# LCD_CONNECTORS.net
KiCad netlist of a schematic drawn in Altium Designer
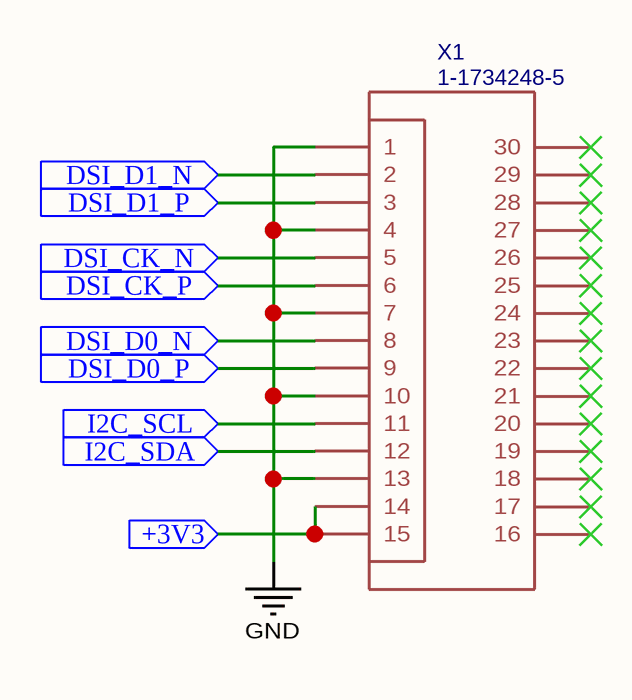
[diagram p0: LCD CONNECTORS.schdoc]

(export (version "E")
  (design (tool "Eeschema 10.0.6"))
  (components
    (comp (ref "X1")
      (value "1-1734248-5")
      (fields (field (name "CONTRIBUTOR") "IBE_Acc"))
      (libsource (lib "altium-import") (part "root_0_1-1734248-5_"))
    )
  )
  (nets
    (net (code "1") (name "/+3V3") (class "Default")
      (node (ref "X1") (pin "14") (pinfunction "14_14") (pintype "passive"))
      (node (ref "X1") (pin "15") (pinfunction "15_15") (pintype "passive"))
    )
    (net (code "2") (name "/DSI_CK_N") (class "Default")
      (node (ref "X1") (pin "5") (pinfunction "5_5") (pintype "passive"))
    )
    (net (code "3") (name "/DSI_CK_P") (class "Default")
      (node (ref "X1") (pin "6") (pinfunction "6_6") (pintype "passive"))
    )
    (net (code "4") (name "/DSI_D0_N") (class "Default")
      (node (ref "X1") (pin "8") (pinfunction "8_8") (pintype "passive"))
    )
    (net (code "5") (name "/DSI_D0_P") (class "Default")
      (node (ref "X1") (pin "9") (pinfunction "9_9") (pintype "passive"))
    )
    (net (code "6") (name "/DSI_D1_N") (class "Default")
      (node (ref "X1") (pin "2") (pinfunction "2_2") (pintype "passive"))
    )
    (net (code "7") (name "/DSI_D1_P") (class "Default")
      (node (ref "X1") (pin "3") (pinfunction "3_3") (pintype "passive"))
    )
    (net (code "8") (name "/I2C_SCL") (class "Default")
      (node (ref "X1") (pin "11") (pinfunction "11_11") (pintype "passive"))
    )
    (net (code "9") (name "/I2C_SDA") (class "Default")
      (node (ref "X1") (pin "12") (pinfunction "12_12") (pintype "passive"))
    )
    (net (code "10") (name "GND") (class "Default")
      (node (ref "X1") (pin "1") (pinfunction "1_1") (pintype "passive"))
      (node (ref "X1") (pin "10") (pinfunction "10_10") (pintype "passive"))
      (node (ref "X1") (pin "13") (pinfunction "13_13") (pintype "passive"))
      (node (ref "X1") (pin "4") (pinfunction "4_4") (pintype "passive"))
      (node (ref "X1") (pin "7") (pinfunction "7_7") (pintype "passive"))
    )
    (net (code "11") (name "unconnected-(X1-Pad16)") (class "Default")
      (node (ref "X1") (pin "16") (pinfunction "16_16") (pintype "passive+no_connect"))
    )
    (net (code "12") (name "unconnected-(X1-Pad17)") (class "Default")
      (node (ref "X1") (pin "17") (pinfunction "17_17") (pintype "passive+no_connect"))
    )
    (net (code "13") (name "unconnected-(X1-Pad18)") (class "Default")
      (node (ref "X1") (pin "18") (pinfunction "18_18") (pintype "passive+no_connect"))
    )
    (net (code "14") (name "unconnected-(X1-Pad19)") (class "Default")
      (node (ref "X1") (pin "19") (pinfunction "19_19") (pintype "passive+no_connect"))
    )
    (net (code "15") (name "unconnected-(X1-Pad20)") (class "Default")
      (node (ref "X1") (pin "20") (pinfunction "20_20") (pintype "passive+no_connect"))
    )
    (net (code "16") (name "unconnected-(X1-Pad21)") (class "Default")
      (node (ref "X1") (pin "21") (pinfunction "21_21") (pintype "passive+no_connect"))
    )
    (net (code "17") (name "unconnected-(X1-Pad22)") (class "Default")
      (node (ref "X1") (pin "22") (pinfunction "22_22") (pintype "passive+no_connect"))
    )
    (net (code "18") (name "unconnected-(X1-Pad23)") (class "Default")
      (node (ref "X1") (pin "23") (pinfunction "23_23") (pintype "passive+no_connect"))
    )
    (net (code "19") (name "unconnected-(X1-Pad24)") (class "Default")
      (node (ref "X1") (pin "24") (pinfunction "24_24") (pintype "passive+no_connect"))
    )
    (net (code "20") (name "unconnected-(X1-Pad25)") (class "Default")
      (node (ref "X1") (pin "25") (pinfunction "25_25") (pintype "passive+no_connect"))
    )
    (net (code "21") (name "unconnected-(X1-Pad26)") (class "Default")
      (node (ref "X1") (pin "26") (pinfunction "26_26") (pintype "passive+no_connect"))
    )
    (net (code "22") (name "unconnected-(X1-Pad27)") (class "Default")
      (node (ref "X1") (pin "27") (pinfunction "27_27") (pintype "passive+no_connect"))
    )
    (net (code "23") (name "unconnected-(X1-Pad28)") (class "Default")
      (node (ref "X1") (pin "28") (pinfunction "28_28") (pintype "passive+no_connect"))
    )
    (net (code "24") (name "unconnected-(X1-Pad29)") (class "Default")
      (node (ref "X1") (pin "29") (pinfunction "29_29") (pintype "passive+no_connect"))
    )
    (net (code "25") (name "unconnected-(X1-Pad30)") (class "Default")
      (node (ref "X1") (pin "30") (pinfunction "30_30") (pintype "passive+no_connect"))
    )
  )
)
